# SME_S8261.net
KiCad netlist of a schematic drawn in Altium Designer
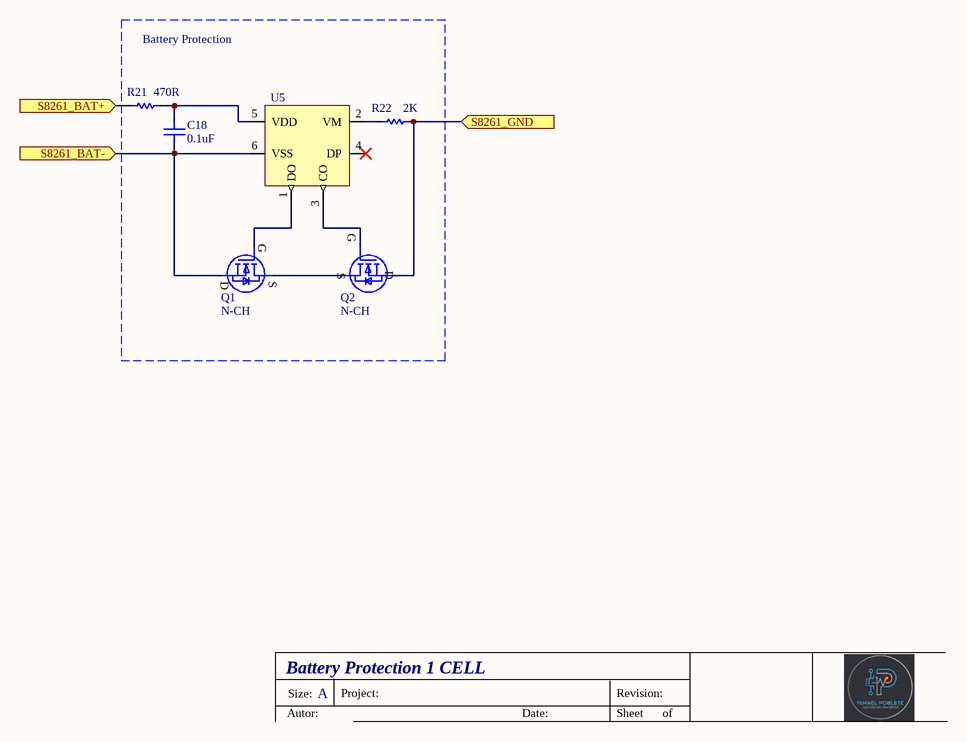
[diagram p0: SME_S8261.SchDoc]

(export (version "E")
  (design (tool "Eeschema 10.0.6"))
  (components
    (comp (ref "C18")
      (value "CC0603KRX7R9BB104")
      (footprint "C0603")
      (description "Multilayer Ceramic Capacitors MLCC - SMD/SMT 50 V 0.1uF X7R 0603 10%")
      (fields (field (name "CAPACITANCE") "0.1uF"))
      (libsource (lib "SME") (part "CC0603KRX7R9BB104"))
    )
    (comp (ref "Q1")
      (value "N-CH")
      (footprint "PowerPAK 1212-8-Pad")
      (description "MOSFET (N-Channel)")
      (fields
        (field (name "MANUFACTURER_PART_NUMBER") "SI7106DN-T1-GE3")
        (field (name "MOUSER PART NUMBER") "781-SI7106DN-T1-GE3")
      )
      (libsource (lib "SME") (part "SI7106DN-T1-GE3"))
    )
    (comp (ref "Q2")
      (value "N-CH")
      (footprint "PowerPAK 1212-8-Pad")
      (description "MOSFET (N-Channel)")
      (fields
        (field (name "MANUFACTURER_PART_NUMBER") "SI7106DN-T1-GE3")
        (field (name "MOUSER PART NUMBER") "781-SI7106DN-T1-GE3")
      )
      (libsource (lib "SME") (part "SI7106DN-T1-GE3"))
    )
    (comp (ref "R21")
      (value "RC0603FR-07470RL")
      (footprint "RES_0603")
      (description "470 Ohms ±1% 0.1W, 1/10W Chip Resistor 0603 (1608 Metric) Moisture Resistant Thick Film")
      (fields (field (name "RESISTANCE") "470R"))
      (libsource (lib "SME") (part "RC0603FR-07470RL"))
    )
    (comp (ref "R22")
      (value "RT0603DRD072KL")
      (footprint "RES_0603")
      (description "Thin Film Resistors - SMD 2K Ohm 0.5% 1/10W 75 Volts 25ppm")
      (fields (field (name "RESISTANCE") "2K"))
      (libsource (lib "SME") (part "RT0603DRD072KL"))
    )
    (comp (ref "U5")
      (value "S-8261AAXMD-G2XT2U")
      (footprint "SOT95P275X135-6N")
      (description "Battery Battery Protection IC Lithium Ion/Polymer SOT-23-6")
      (libsource (lib "SME") (part "S-8261AAXMD-G2XT2U"))
    )
  )
  (nets
    (net (code "1") (name "/S8261_BAT+") (class "Default")
      (node (ref "R21") (pin "1") (pinfunction "1_1") (pintype "passive"))
    )
    (net (code "2") (name "/S8261_BAT-") (class "Default")
      (node (ref "C18") (pin "1") (pinfunction "1_1") (pintype "passive"))
      (node (ref "Q1") (pin "3") (pinfunction "D_3") (pintype "passive"))
      (node (ref "U5") (pin "6") (pinfunction "VSS_6") (pintype "passive"))
    )
    (net (code "3") (name "/S8261_GND") (class "Default")
      (node (ref "Q2") (pin "3") (pinfunction "D_3") (pintype "passive"))
      (node (ref "R22") (pin "2") (pinfunction "2_2") (pintype "passive"))
    )
    (net (code "4") (name "Net-(Q1-G)") (class "Default")
      (node (ref "Q1") (pin "2") (pinfunction "G_2") (pintype "passive"))
      (node (ref "U5") (pin "1") (pinfunction "DO_1") (pintype "output"))
    )
    (net (code "5") (name "Net-(Q1-S)") (class "Default")
      (node (ref "Q1") (pin "1") (pinfunction "S_1") (pintype "passive"))
      (node (ref "Q2") (pin "1") (pinfunction "S_1") (pintype "passive"))
    )
    (net (code "6") (name "Net-(Q2-G)") (class "Default")
      (node (ref "Q2") (pin "2") (pinfunction "G_2") (pintype "passive"))
      (node (ref "U5") (pin "3") (pinfunction "CO_3") (pintype "output"))
    )
    (net (code "7") (name "Net-(U5-VDD)") (class "Default")
      (node (ref "C18") (pin "2") (pinfunction "2_2") (pintype "passive"))
      (node (ref "R21") (pin "2") (pinfunction "2_2") (pintype "passive"))
      (node (ref "U5") (pin "5") (pinfunction "VDD_5") (pintype "passive"))
    )
    (net (code "8") (name "Net-(U5-VM)") (class "Default")
      (node (ref "R22") (pin "1") (pinfunction "1_1") (pintype "passive"))
      (node (ref "U5") (pin "2") (pinfunction "VM_2") (pintype "passive"))
    )
    (net (code "9") (name "unconnected-(U5-DP-Pad4)") (class "Default")
      (node (ref "U5") (pin "4") (pinfunction "DP_4") (pintype "passive+no_connect"))
    )
  )
)
